# LEDSync_AR.net
KiCad netlist of a schematic drawn in EAGLE
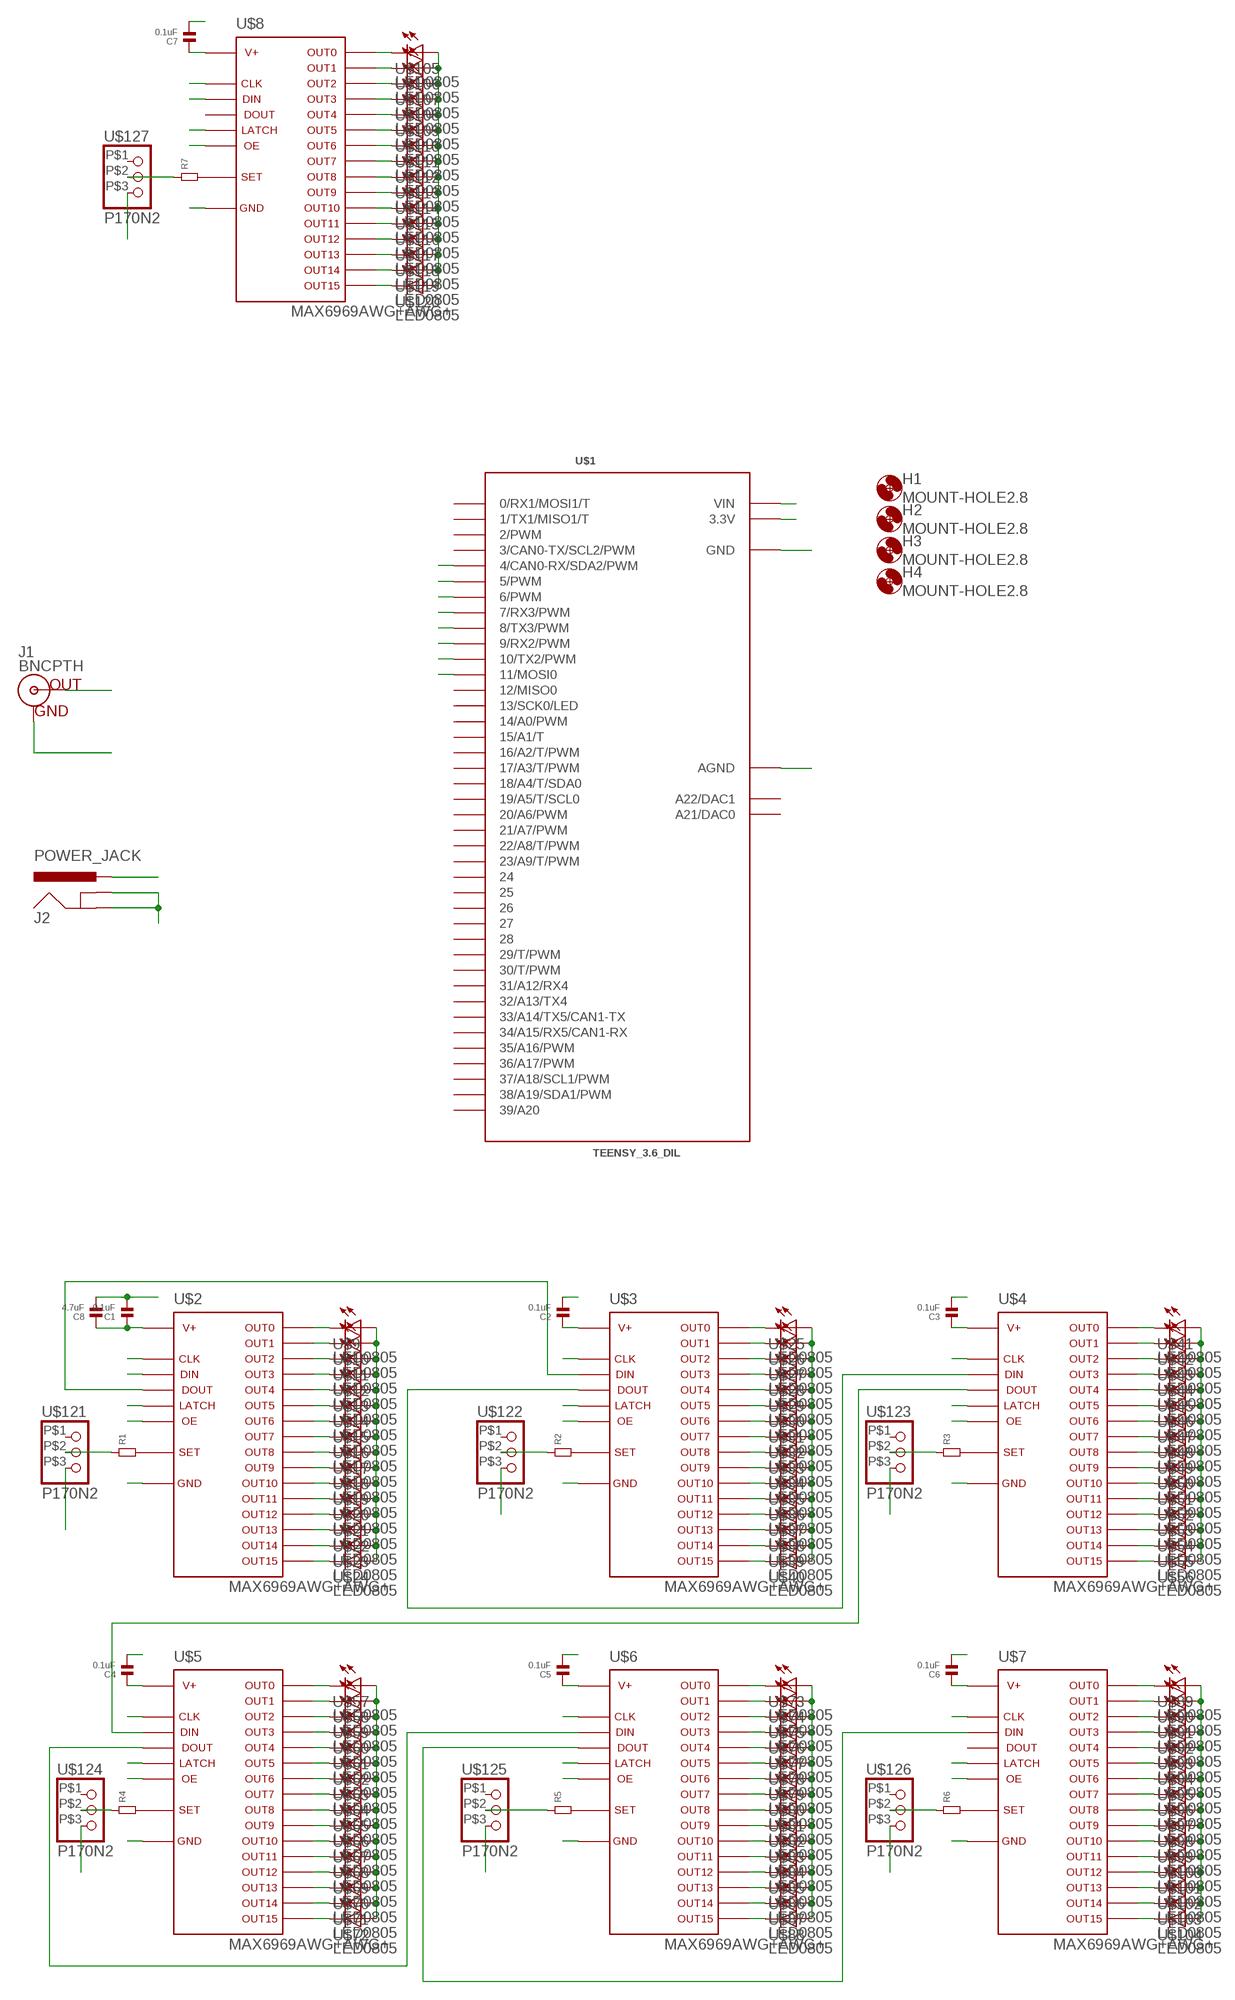
[diagram p0: schematic, sheet 1]

(export (version "E")
  (design (tool "Eeschema 10.0.6"))
  (components
    (comp (ref "C1")
      (value "0.1uF")
      (footprint "eagle-import:0805")
      (libsource (lib "eagle-import") (part "CAPACITOR.0805"))
    )
    (comp (ref "C2")
      (value "0.1uF")
      (footprint "eagle-import:0805")
      (libsource (lib "eagle-import") (part "CAPACITOR.0805"))
    )
    (comp (ref "C3")
      (value "0.1uF")
      (footprint "eagle-import:0805")
      (libsource (lib "eagle-import") (part "CAPACITOR.0805"))
    )
    (comp (ref "C4")
      (value "0.1uF")
      (footprint "eagle-import:0805")
      (libsource (lib "eagle-import") (part "CAPACITOR.0805"))
    )
    (comp (ref "C5")
      (value "0.1uF")
      (footprint "eagle-import:0805")
      (libsource (lib "eagle-import") (part "CAPACITOR.0805"))
    )
    (comp (ref "C6")
      (value "0.1uF")
      (footprint "eagle-import:0805")
      (libsource (lib "eagle-import") (part "CAPACITOR.0805"))
    )
    (comp (ref "C7")
      (value "0.1uF")
      (footprint "eagle-import:0805")
      (libsource (lib "eagle-import") (part "CAPACITOR.0805"))
    )
    (comp (ref "C8")
      (value "4.7uF")
      (footprint "eagle-import:0805")
      (libsource (lib "eagle-import") (part "CAPACITOR.0805"))
    )
    (comp (ref "H1")
      (value "MOUNT-HOLE2.8")
      (footprint "eagle-import:2,8")
      (libsource (lib "eagle-import") (part "MOUNT-HOLE2.8"))
    )
    (comp (ref "H2")
      (value "MOUNT-HOLE2.8")
      (footprint "eagle-import:2,8")
      (libsource (lib "eagle-import") (part "MOUNT-HOLE2.8"))
    )
    (comp (ref "H3")
      (value "MOUNT-HOLE2.8")
      (footprint "eagle-import:2,8")
      (libsource (lib "eagle-import") (part "MOUNT-HOLE2.8"))
    )
    (comp (ref "H4")
      (value "MOUNT-HOLE2.8")
      (footprint "eagle-import:2,8")
      (libsource (lib "eagle-import") (part "MOUNT-HOLE2.8"))
    )
    (comp (ref "J1")
      (value "BNCPTH")
      (footprint "eagle-import:BNC")
      (libsource (lib "eagle-import") (part "BNCPTH"))
    )
    (comp (ref "J2")
      (value "POWER_JACK")
      (footprint "eagle-import:POWER_JACK_PTH")
      (libsource (lib "eagle-import") (part "POWER_JACK"))
    )
    (comp (ref "R1")
      (value "RESISTOR.0805")
      (footprint "eagle-import:0805")
      (libsource (lib "eagle-import") (part "RESISTOR.0805"))
    )
    (comp (ref "R2")
      (value "RESISTOR.0805")
      (footprint "eagle-import:0805")
      (libsource (lib "eagle-import") (part "RESISTOR.0805"))
    )
    (comp (ref "R3")
      (value "RESISTOR.0805")
      (footprint "eagle-import:0805")
      (libsource (lib "eagle-import") (part "RESISTOR.0805"))
    )
    (comp (ref "R4")
      (value "RESISTOR.0805")
      (footprint "eagle-import:0805")
      (libsource (lib "eagle-import") (part "RESISTOR.0805"))
    )
    (comp (ref "R5")
      (value "RESISTOR.0805")
      (footprint "eagle-import:0805")
      (libsource (lib "eagle-import") (part "RESISTOR.0805"))
    )
    (comp (ref "R6")
      (value "RESISTOR.0805")
      (footprint "eagle-import:0805")
      (libsource (lib "eagle-import") (part "RESISTOR.0805"))
    )
    (comp (ref "R7")
      (value "RESISTOR.0805")
      (footprint "eagle-import:0805")
      (libsource (lib "eagle-import") (part "RESISTOR.0805"))
    )
    (comp (ref "U$1")
      (value "TEENSY_3.6_DIL")
      (footprint "eagle-import:TEENSY_3.6_DIL")
      (libsource (lib "eagle-import") (part "TEENSY_3.6_DIL"))
    )
    (comp (ref "U$2")
      (value "MAX6969AWG+AWG+")
      (footprint "eagle-import:SO24L")
      (libsource (lib "eagle-import") (part "MAX6969AWG+AWG+"))
    )
    (comp (ref "U$3")
      (value "MAX6969AWG+AWG+")
      (footprint "eagle-import:SO24L")
      (libsource (lib "eagle-import") (part "MAX6969AWG+AWG+"))
    )
    (comp (ref "U$4")
      (value "MAX6969AWG+AWG+")
      (footprint "eagle-import:SO24L")
      (libsource (lib "eagle-import") (part "MAX6969AWG+AWG+"))
    )
    (comp (ref "U$5")
      (value "MAX6969AWG+AWG+")
      (footprint "eagle-import:SO24L")
      (libsource (lib "eagle-import") (part "MAX6969AWG+AWG+"))
    )
    (comp (ref "U$6")
      (value "MAX6969AWG+AWG+")
      (footprint "eagle-import:SO24L")
      (libsource (lib "eagle-import") (part "MAX6969AWG+AWG+"))
    )
    (comp (ref "U$7")
      (value "MAX6969AWG+AWG+")
      (footprint "eagle-import:SO24L")
      (libsource (lib "eagle-import") (part "MAX6969AWG+AWG+"))
    )
    (comp (ref "U$8")
      (value "MAX6969AWG+AWG+")
      (footprint "eagle-import:SO24L")
      (libsource (lib "eagle-import") (part "MAX6969AWG+AWG+"))
    )
    (comp (ref "U$9")
      (value "LED0805")
      (footprint "eagle-import:0805")
      (libsource (lib "eagle-import") (part "LED0805"))
    )
    (comp (ref "U$10")
      (value "LED0805")
      (footprint "eagle-import:0805")
      (libsource (lib "eagle-import") (part "LED0805"))
    )
    (comp (ref "U$11")
      (value "LED0805")
      (footprint "eagle-import:0805")
      (libsource (lib "eagle-import") (part "LED0805"))
    )
    (comp (ref "U$12")
      (value "LED0805")
      (footprint "eagle-import:0805")
      (libsource (lib "eagle-import") (part "LED0805"))
    )
    (comp (ref "U$13")
      (value "LED0805")
      (footprint "eagle-import:0805")
      (libsource (lib "eagle-import") (part "LED0805"))
    )
    (comp (ref "U$14")
      (value "LED0805")
      (footprint "eagle-import:0805")
      (libsource (lib "eagle-import") (part "LED0805"))
    )
    (comp (ref "U$15")
      (value "LED0805")
      (footprint "eagle-import:0805")
      (libsource (lib "eagle-import") (part "LED0805"))
    )
    (comp (ref "U$16")
      (value "LED0805")
      (footprint "eagle-import:0805")
      (libsource (lib "eagle-import") (part "LED0805"))
    )
    (comp (ref "U$17")
      (value "LED0805")
      (footprint "eagle-import:0805")
      (libsource (lib "eagle-import") (part "LED0805"))
    )
    (comp (ref "U$18")
      (value "LED0805")
      (footprint "eagle-import:0805")
      (libsource (lib "eagle-import") (part "LED0805"))
    )
    (comp (ref "U$19")
      (value "LED0805")
      (footprint "eagle-import:0805")
      (libsource (lib "eagle-import") (part "LED0805"))
    )
    (comp (ref "U$20")
      (value "LED0805")
      (footprint "eagle-import:0805")
      (libsource (lib "eagle-import") (part "LED0805"))
    )
    (comp (ref "U$21")
      (value "LED0805")
      (footprint "eagle-import:0805")
      (libsource (lib "eagle-import") (part "LED0805"))
    )
    (comp (ref "U$22")
      (value "LED0805")
      (footprint "eagle-import:0805")
      (libsource (lib "eagle-import") (part "LED0805"))
    )
    (comp (ref "U$23")
      (value "LED0805")
      (footprint "eagle-import:0805")
      (libsource (lib "eagle-import") (part "LED0805"))
    )
    (comp (ref "U$24")
      (value "LED0805")
      (footprint "eagle-import:0805")
      (libsource (lib "eagle-import") (part "LED0805"))
    )
    (comp (ref "U$25")
      (value "LED0805")
      (footprint "eagle-import:0805")
      (libsource (lib "eagle-import") (part "LED0805"))
    )
    (comp (ref "U$26")
      (value "LED0805")
      (footprint "eagle-import:0805")
      (libsource (lib "eagle-import") (part "LED0805"))
    )
    (comp (ref "U$27")
      (value "LED0805")
      (footprint "eagle-import:0805")
      (libsource (lib "eagle-import") (part "LED0805"))
    )
    (comp (ref "U$28")
      (value "LED0805")
      (footprint "eagle-import:0805")
      (libsource (lib "eagle-import") (part "LED0805"))
    )
    (comp (ref "U$29")
      (value "LED0805")
      (footprint "eagle-import:0805")
      (libsource (lib "eagle-import") (part "LED0805"))
    )
    (comp (ref "U$30")
      (value "LED0805")
      (footprint "eagle-import:0805")
      (libsource (lib "eagle-import") (part "LED0805"))
    )
    (comp (ref "U$31")
      (value "LED0805")
      (footprint "eagle-import:0805")
      (libsource (lib "eagle-import") (part "LED0805"))
    )
    (comp (ref "U$32")
      (value "LED0805")
      (footprint "eagle-import:0805")
      (libsource (lib "eagle-import") (part "LED0805"))
    )
    (comp (ref "U$33")
      (value "LED0805")
      (footprint "eagle-import:0805")
      (libsource (lib "eagle-import") (part "LED0805"))
    )
    (comp (ref "U$34")
      (value "LED0805")
      (footprint "eagle-import:0805")
      (libsource (lib "eagle-import") (part "LED0805"))
    )
    (comp (ref "U$35")
      (value "LED0805")
      (footprint "eagle-import:0805")
      (libsource (lib "eagle-import") (part "LED0805"))
    )
    (comp (ref "U$36")
      (value "LED0805")
      (footprint "eagle-import:0805")
      (libsource (lib "eagle-import") (part "LED0805"))
    )
    (comp (ref "U$37")
      (value "LED0805")
      (footprint "eagle-import:0805")
      (libsource (lib "eagle-import") (part "LED0805"))
    )
    (comp (ref "U$38")
      (value "LED0805")
      (footprint "eagle-import:0805")
      (libsource (lib "eagle-import") (part "LED0805"))
    )
    (comp (ref "U$39")
      (value "LED0805")
      (footprint "eagle-import:0805")
      (libsource (lib "eagle-import") (part "LED0805"))
    )
    (comp (ref "U$40")
      (value "LED0805")
      (footprint "eagle-import:0805")
      (libsource (lib "eagle-import") (part "LED0805"))
    )
    (comp (ref "U$41")
      (value "LED0805")
      (footprint "eagle-import:0805")
      (libsource (lib "eagle-import") (part "LED0805"))
    )
    (comp (ref "U$42")
      (value "LED0805")
      (footprint "eagle-import:0805")
      (libsource (lib "eagle-import") (part "LED0805"))
    )
    (comp (ref "U$43")
      (value "LED0805")
      (footprint "eagle-import:0805")
      (libsource (lib "eagle-import") (part "LED0805"))
    )
    (comp (ref "U$44")
      (value "LED0805")
      (footprint "eagle-import:0805")
      (libsource (lib "eagle-import") (part "LED0805"))
    )
    (comp (ref "U$45")
      (value "LED0805")
      (footprint "eagle-import:0805")
      (libsource (lib "eagle-import") (part "LED0805"))
    )
    (comp (ref "U$46")
      (value "LED0805")
      (footprint "eagle-import:0805")
      (libsource (lib "eagle-import") (part "LED0805"))
    )
    (comp (ref "U$47")
      (value "LED0805")
      (footprint "eagle-import:0805")
      (libsource (lib "eagle-import") (part "LED0805"))
    )
    (comp (ref "U$48")
      (value "LED0805")
      (footprint "eagle-import:0805")
      (libsource (lib "eagle-import") (part "LED0805"))
    )
    (comp (ref "U$49")
      (value "LED0805")
      (footprint "eagle-import:0805")
      (libsource (lib "eagle-import") (part "LED0805"))
    )
    (comp (ref "U$50")
      (value "LED0805")
      (footprint "eagle-import:0805")
      (libsource (lib "eagle-import") (part "LED0805"))
    )
    (comp (ref "U$51")
      (value "LED0805")
      (footprint "eagle-import:0805")
      (libsource (lib "eagle-import") (part "LED0805"))
    )
    (comp (ref "U$52")
      (value "LED0805")
      (footprint "eagle-import:0805")
      (libsource (lib "eagle-import") (part "LED0805"))
    )
    (comp (ref "U$53")
      (value "LED0805")
      (footprint "eagle-import:0805")
      (libsource (lib "eagle-import") (part "LED0805"))
    )
    (comp (ref "U$54")
      (value "LED0805")
      (footprint "eagle-import:0805")
      (libsource (lib "eagle-import") (part "LED0805"))
    )
    (comp (ref "U$55")
      (value "LED0805")
      (footprint "eagle-import:0805")
      (libsource (lib "eagle-import") (part "LED0805"))
    )
    (comp (ref "U$56")
      (value "LED0805")
      (footprint "eagle-import:0805")
      (libsource (lib "eagle-import") (part "LED0805"))
    )
    (comp (ref "U$57")
      (value "LED0805")
      (footprint "eagle-import:0805")
      (libsource (lib "eagle-import") (part "LED0805"))
    )
    (comp (ref "U$58")
      (value "LED0805")
      (footprint "eagle-import:0805")
      (libsource (lib "eagle-import") (part "LED0805"))
    )
    (comp (ref "U$59")
      (value "LED0805")
      (footprint "eagle-import:0805")
      (libsource (lib "eagle-import") (part "LED0805"))
    )
    (comp (ref "U$60")
      (value "LED0805")
      (footprint "eagle-import:0805")
      (libsource (lib "eagle-import") (part "LED0805"))
    )
    (comp (ref "U$61")
      (value "LED0805")
      (footprint "eagle-import:0805")
      (libsource (lib "eagle-import") (part "LED0805"))
    )
    (comp (ref "U$62")
      (value "LED0805")
      (footprint "eagle-import:0805")
      (libsource (lib "eagle-import") (part "LED0805"))
    )
    (comp (ref "U$63")
      (value "LED0805")
      (footprint "eagle-import:0805")
      (libsource (lib "eagle-import") (part "LED0805"))
    )
    (comp (ref "U$64")
      (value "LED0805")
      (footprint "eagle-import:0805")
      (libsource (lib "eagle-import") (part "LED0805"))
    )
    (comp (ref "U$65")
      (value "LED0805")
      (footprint "eagle-import:0805")
      (libsource (lib "eagle-import") (part "LED0805"))
    )
    (comp (ref "U$66")
      (value "LED0805")
      (footprint "eagle-import:0805")
      (libsource (lib "eagle-import") (part "LED0805"))
    )
    (comp (ref "U$67")
      (value "LED0805")
      (footprint "eagle-import:0805")
      (libsource (lib "eagle-import") (part "LED0805"))
    )
    (comp (ref "U$68")
      (value "LED0805")
      (footprint "eagle-import:0805")
      (libsource (lib "eagle-import") (part "LED0805"))
    )
    (comp (ref "U$69")
      (value "LED0805")
      (footprint "eagle-import:0805")
      (libsource (lib "eagle-import") (part "LED0805"))
    )
    (comp (ref "U$70")
      (value "LED0805")
      (footprint "eagle-import:0805")
      (libsource (lib "eagle-import") (part "LED0805"))
    )
    (comp (ref "U$71")
      (value "LED0805")
      (footprint "eagle-import:0805")
      (libsource (lib "eagle-import") (part "LED0805"))
    )
    (comp (ref "U$72")
      (value "LED0805")
      (footprint "eagle-import:0805")
      (libsource (lib "eagle-import") (part "LED0805"))
    )
    (comp (ref "U$73")
      (value "LED0805")
      (footprint "eagle-import:0805")
      (libsource (lib "eagle-import") (part "LED0805"))
    )
    (comp (ref "U$74")
      (value "LED0805")
      (footprint "eagle-import:0805")
      (libsource (lib "eagle-import") (part "LED0805"))
    )
    (comp (ref "U$75")
      (value "LED0805")
      (footprint "eagle-import:0805")
      (libsource (lib "eagle-import") (part "LED0805"))
    )
    (comp (ref "U$76")
      (value "LED0805")
      (footprint "eagle-import:0805")
      (libsource (lib "eagle-import") (part "LED0805"))
    )
    (comp (ref "U$77")
      (value "LED0805")
      (footprint "eagle-import:0805")
      (libsource (lib "eagle-import") (part "LED0805"))
    )
    (comp (ref "U$78")
      (value "LED0805")
      (footprint "eagle-import:0805")
      (libsource (lib "eagle-import") (part "LED0805"))
    )
    (comp (ref "U$79")
      (value "LED0805")
      (footprint "eagle-import:0805")
      (libsource (lib "eagle-import") (part "LED0805"))
    )
    (comp (ref "U$80")
      (value "LED0805")
      (footprint "eagle-import:0805")
      (libsource (lib "eagle-import") (part "LED0805"))
    )
    (comp (ref "U$81")
      (value "LED0805")
      (footprint "eagle-import:0805")
      (libsource (lib "eagle-import") (part "LED0805"))
    )
    (comp (ref "U$82")
      (value "LED0805")
      (footprint "eagle-import:0805")
      (libsource (lib "eagle-import") (part "LED0805"))
    )
    (comp (ref "U$83")
      (value "LED0805")
      (footprint "eagle-import:0805")
      (libsource (lib "eagle-import") (part "LED0805"))
    )
    (comp (ref "U$84")
      (value "LED0805")
      (footprint "eagle-import:0805")
      (libsource (lib "eagle-import") (part "LED0805"))
    )
    (comp (ref "U$85")
      (value "LED0805")
      (footprint "eagle-import:0805")
      (libsource (lib "eagle-import") (part "LED0805"))
    )
    (comp (ref "U$86")
      (value "LED0805")
      (footprint "eagle-import:0805")
      (libsource (lib "eagle-import") (part "LED0805"))
    )
    (comp (ref "U$87")
      (value "LED0805")
      (footprint "eagle-import:0805")
      (libsource (lib "eagle-import") (part "LED0805"))
    )
    (comp (ref "U$88")
      (value "LED0805")
      (footprint "eagle-import:0805")
      (libsource (lib "eagle-import") (part "LED0805"))
    )
    (comp (ref "U$89")
      (value "LED0805")
      (footprint "eagle-import:0805")
      (libsource (lib "eagle-import") (part "LED0805"))
    )
    (comp (ref "U$90")
      (value "LED0805")
      (footprint "eagle-import:0805")
      (libsource (lib "eagle-import") (part "LED0805"))
    )
    (comp (ref "U$91")
      (value "LED0805")
      (footprint "eagle-import:0805")
      (libsource (lib "eagle-import") (part "LED0805"))
    )
    (comp (ref "U$92")
      (value "LED0805")
      (footprint "eagle-import:0805")
      (libsource (lib "eagle-import") (part "LED0805"))
    )
    (comp (ref "U$93")
      (value "LED0805")
      (footprint "eagle-import:0805")
      (libsource (lib "eagle-import") (part "LED0805"))
    )
    (comp (ref "U$94")
      (value "LED0805")
      (footprint "eagle-import:0805")
      (libsource (lib "eagle-import") (part "LED0805"))
    )
    (comp (ref "U$95")
      (value "LED0805")
      (footprint "eagle-import:0805")
      (libsource (lib "eagle-import") (part "LED0805"))
    )
    (comp (ref "U$96")
      (value "LED0805")
      (footprint "eagle-import:0805")
      (libsource (lib "eagle-import") (part "LED0805"))
    )
    (comp (ref "U$97")
      (value "LED0805")
      (footprint "eagle-import:0805")
      (libsource (lib "eagle-import") (part "LED0805"))
    )
    (comp (ref "U$98")
      (value "LED0805")
      (footprint "eagle-import:0805")
      (libsource (lib "eagle-import") (part "LED0805"))
    )
    (comp (ref "U$99")
      (value "LED0805")
      (footprint "eagle-import:0805")
      (libsource (lib "eagle-import") (part "LED0805"))
    )
    (comp (ref "U$100")
      (value "LED0805")
      (footprint "eagle-import:0805")
      (libsource (lib "eagle-import") (part "LED0805"))
    )
    (comp (ref "U$101")
      (value "LED0805")
      (footprint "eagle-import:0805")
      (libsource (lib "eagle-import") (part "LED0805"))
    )
    (comp (ref "U$102")
      (value "LED0805")
      (footprint "eagle-import:0805")
      (libsource (lib "eagle-import") (part "LED0805"))
    )
    (comp (ref "U$103")
      (value "LED0805")
      (footprint "eagle-import:0805")
      (libsource (lib "eagle-import") (part "LED0805"))
    )
    (comp (ref "U$104")
      (value "LED0805")
      (footprint "eagle-import:0805")
      (libsource (lib "eagle-import") (part "LED0805"))
    )
    (comp (ref "U$105")
      (value "LED0805")
      (footprint "eagle-import:0805")
      (libsource (lib "eagle-import") (part "LED0805"))
    )
    (comp (ref "U$106")
      (value "LED0805")
      (footprint "eagle-import:0805")
      (libsource (lib "eagle-import") (part "LED0805"))
    )
    (comp (ref "U$107")
      (value "LED0805")
      (footprint "eagle-import:0805")
      (libsource (lib "eagle-import") (part "LED0805"))
    )
    (comp (ref "U$108")
      (value "LED0805")
      (footprint "eagle-import:0805")
      (libsource (lib "eagle-import") (part "LED0805"))
    )
    (comp (ref "U$109")
      (value "LED0805")
      (footprint "eagle-import:0805")
      (libsource (lib "eagle-import") (part "LED0805"))
    )
    (comp (ref "U$110")
      (value "LED0805")
      (footprint "eagle-import:0805")
      (libsource (lib "eagle-import") (part "LED0805"))
    )
    (comp (ref "U$111")
      (value "LED0805")
      (footprint "eagle-import:0805")
      (libsource (lib "eagle-import") (part "LED0805"))
    )
    (comp (ref "U$112")
      (value "LED0805")
      (footprint "eagle-import:0805")
      (libsource (lib "eagle-import") (part "LED0805"))
    )
    (comp (ref "U$113")
      (value "LED0805")
      (footprint "eagle-import:0805")
      (libsource (lib "eagle-import") (part "LED0805"))
    )
    (comp (ref "U$114")
      (value "LED0805")
      (footprint "eagle-import:0805")
      (libsource (lib "eagle-import") (part "LED0805"))
    )
    (comp (ref "U$115")
      (value "LED0805")
      (footprint "eagle-import:0805")
      (libsource (lib "eagle-import") (part "LED0805"))
    )
    (comp (ref "U$116")
      (value "LED0805")
      (footprint "eagle-import:0805")
      (libsource (lib "eagle-import") (part "LED0805"))
    )
    (comp (ref "U$117")
      (value "LED0805")
      (footprint "eagle-import:0805")
      (libsource (lib "eagle-import") (part "LED0805"))
    )
    (comp (ref "U$118")
      (value "LED0805")
      (footprint "eagle-import:0805")
      (libsource (lib "eagle-import") (part "LED0805"))
    )
    (comp (ref "U$119")
      (value "LED0805")
      (footprint "eagle-import:0805")
      (libsource (lib "eagle-import") (part "LED0805"))
    )
    (comp (ref "U$120")
      (value "LED0805")
      (footprint "eagle-import:0805")
      (libsource (lib "eagle-import") (part "LED0805"))
    )
    (comp (ref "U$121")
      (value "P170N2")
      (footprint "eagle-import:P170N2")
      (libsource (lib "eagle-import") (part "P170N2"))
    )
    (comp (ref "U$122")
      (value "P170N2")
      (footprint "eagle-import:P170N2")
      (libsource (lib "eagle-import") (part "P170N2"))
    )
    (comp (ref "U$123")
      (value "P170N2")
      (footprint "eagle-import:P170N2")
      (libsource (lib "eagle-import") (part "P170N2"))
    )
    (comp (ref "U$124")
      (value "P170N2")
      (footprint "eagle-import:P170N2")
      (libsource (lib "eagle-import") (part "P170N2"))
    )
    (comp (ref "U$125")
      (value "P170N2")
      (footprint "eagle-import:P170N2")
      (libsource (lib "eagle-import") (part "P170N2"))
    )
    (comp (ref "U$126")
      (value "P170N2")
      (footprint "eagle-import:P170N2")
      (libsource (lib "eagle-import") (part "P170N2"))
    )
    (comp (ref "U$127")
      (value "P170N2")
      (footprint "eagle-import:P170N2")
      (libsource (lib "eagle-import") (part "P170N2"))
    )
  )
  (nets
    (net (code "1") (name "/GND") (class "Default")
      (node (ref "C1") (pin "2") (pinfunction "2_2") (pintype "bidirectional"))
      (node (ref "C2") (pin "2") (pinfunction "2_2") (pintype "bidirectional"))
      (node (ref "C3") (pin "2") (pinfunction "2_2") (pintype "bidirectional"))
      (node (ref "C4") (pin "2") (pinfunction "2_2") (pintype "bidirectional"))
      (node (ref "C5") (pin "2") (pinfunction "2_2") (pintype "bidirectional"))
      (node (ref "C6") (pin "2") (pinfunction "2_2") (pintype "bidirectional"))
      (node (ref "C7") (pin "2") (pinfunction "2_2") (pintype "bidirectional"))
      (node (ref "C8") (pin "2") (pinfunction "2_2") (pintype "bidirectional"))
      (node (ref "J1") (pin "GND") (pinfunction "GND_GND") (pintype "bidirectional"))
      (node (ref "J2") (pin "GND") (pinfunction "GND_GND") (pintype "bidirectional"))
      (node (ref "J2") (pin "GNDBREAK") (pinfunction "GNDBREAK_GNDBREAK") (pintype "bidirectional"))
      (node (ref "U$1") (pin "AGND") (pinfunction "AGND_AGND") (pintype "power_in"))
      (node (ref "U$1") (pin "GND") (pinfunction "GND_GND") (pintype "power_in"))
      (node (ref "U$1") (pin "GND1") (pinfunction "GND_GND1") (pintype "power_in"))
      (node (ref "U$121") (pin "P$3") (pinfunction "3_P$3") (pintype "passive"))
      (node (ref "U$122") (pin "P$3") (pinfunction "3_P$3") (pintype "passive"))
      (node (ref "U$123") (pin "P$3") (pinfunction "3_P$3") (pintype "passive"))
      (node (ref "U$124") (pin "P$3") (pinfunction "3_P$3") (pintype "passive"))
      (node (ref "U$125") (pin "P$3") (pinfunction "3_P$3") (pintype "passive"))
      (node (ref "U$126") (pin "P$3") (pinfunction "3_P$3") (pintype "passive"))
      (node (ref "U$127") (pin "P$3") (pinfunction "3_P$3") (pintype "passive"))
      (node (ref "U$2") (pin "1") (pinfunction "P$1_1") (pintype "power_in"))
      (node (ref "U$3") (pin "1") (pinfunction "P$1_1") (pintype "power_in"))
      (node (ref "U$4") (pin "1") (pinfunction "P$1_1") (pintype "power_in"))
      (node (ref "U$5") (pin "1") (pinfunction "P$1_1") (pintype "power_in"))
      (node (ref "U$6") (pin "1") (pinfunction "P$1_1") (pintype "power_in"))
      (node (ref "U$7") (pin "1") (pinfunction "P$1_1") (pintype "power_in"))
      (node (ref "U$8") (pin "1") (pinfunction "P$1_1") (pintype "power_in"))
    )
    (net (code "2") (name "/G_CLK") (class "Default")
      (node (ref "U$1") (pin "5") (pinfunction "5/PWM_5") (pintype "bidirectional"))
      (node (ref "U$2") (pin "3") (pinfunction "P$3_3") (pintype "input"))
      (node (ref "U$3") (pin "3") (pinfunction "P$3_3") (pintype "input"))
      (node (ref "U$4") (pin "3") (pinfunction "P$3_3") (pintype "input"))
      (node (ref "U$5") (pin "3") (pinfunction "P$3_3") (pintype "input"))
      (node (ref "U$6") (pin "3") (pinfunction "P$3_3") (pintype "input"))
      (node (ref "U$7") (pin "3") (pinfunction "P$3_3") (pintype "input"))
    )
    (net (code "3") (name "/G_D") (class "Default")
      (node (ref "U$1") (pin "4") (pinfunction "4/CAN0-RX/SDA2/PWM_4") (pintype "bidirectional"))
      (node (ref "U$2") (pin "2") (pinfunction "P$2_2") (pintype "input"))
    )
    (net (code "4") (name "/G_LE") (class "Default")
      (node (ref "J1") (pin "S") (pinfunction "OUT_S") (pintype "bidirectional"))
      (node (ref "U$1") (pin "6") (pinfunction "6/PWM_6") (pintype "bidirectional"))
      (node (ref "U$2") (pin "4") (pinfunction "P$4_4") (pintype "input"))
      (node (ref "U$3") (pin "4") (pinfunction "P$4_4") (pintype "input"))
      (node (ref "U$4") (pin "4") (pinfunction "P$4_4") (pintype "input"))
      (node (ref "U$5") (pin "4") (pinfunction "P$4_4") (pintype "input"))
      (node (ref "U$6") (pin "4") (pinfunction "P$4_4") (pintype "input"))
      (node (ref "U$7") (pin "4") (pinfunction "P$4_4") (pintype "input"))
    )
    (net (code "5") (name "/G_OE") (class "Default")
      (node (ref "U$1") (pin "7") (pinfunction "7/RX3/PWM_7") (pintype "bidirectional"))
      (node (ref "U$2") (pin "21") (pinfunction "P$21_21") (pintype "input"))
      (node (ref "U$3") (pin "21") (pinfunction "P$21_21") (pintype "input"))
      (node (ref "U$4") (pin "21") (pinfunction "P$21_21") (pintype "input"))
      (node (ref "U$5") (pin "21") (pinfunction "P$21_21") (pintype "input"))
      (node (ref "U$6") (pin "21") (pinfunction "P$21_21") (pintype "input"))
      (node (ref "U$7") (pin "21") (pinfunction "P$21_21") (pintype "input"))
    )
    (net (code "6") (name "/T_CLK") (class "Default")
      (node (ref "U$1") (pin "9") (pinfunction "9/RX2/PWM_9") (pintype "bidirectional"))
      (node (ref "U$8") (pin "3") (pinfunction "P$3_3") (pintype "input"))
    )
    (net (code "7") (name "/T_D") (class "Default")
      (node (ref "U$1") (pin "8") (pinfunction "8/TX3/PWM_8") (pintype "bidirectional"))
      (node (ref "U$8") (pin "2") (pinfunction "P$2_2") (pintype "input"))
    )
    (net (code "8") (name "/T_LE") (class "Default")
      (node (ref "U$1") (pin "10") (pinfunction "10/TX2/PWM_10") (pintype "bidirectional"))
      (node (ref "U$8") (pin "4") (pinfunction "P$4_4") (pintype "input"))
    )
    (net (code "9") (name "/T_OE") (class "Default")
      (node (ref "U$1") (pin "11") (pinfunction "11/MOSI0_11") (pintype "bidirectional"))
      (node (ref "U$8") (pin "21") (pinfunction "P$21_21") (pintype "input"))
    )
    (net (code "10") (name "/VIN") (class "Default")
      (node (ref "C1") (pin "1") (pinfunction "1_1") (pintype "bidirectional"))
      (node (ref "C2") (pin "1") (pinfunction "1_1") (pintype "bidirectional"))
      (node (ref "C3") (pin "1") (pinfunction "1_1") (pintype "bidirectional"))
      (node (ref "C4") (pin "1") (pinfunction "1_1") (pintype "bidirectional"))
      (node (ref "C5") (pin "1") (pinfunction "1_1") (pintype "bidirectional"))
      (node (ref "C6") (pin "1") (pinfunction "1_1") (pintype "bidirectional"))
      (node (ref "C7") (pin "1") (pinfunction "1_1") (pintype "bidirectional"))
      (node (ref "C8") (pin "1") (pinfunction "1_1") (pintype "bidirectional"))
      (node (ref "J2") (pin "PWR") (pinfunction "PWR_PWR") (pintype "bidirectional"))
      (node (ref "U$1") (pin "VIN") (pinfunction "VIN_VIN") (pintype "power_in"))
      (node (ref "U$10") (pin "1") (pinfunction "A_1") (pintype "passive"))
      (node (ref "U$100") (pin "1") (pinfunction "A_1") (pintype "passive"))
      (node (ref "U$101") (pin "1") (pinfunction "A_1") (pintype "passive"))
      (node (ref "U$102") (pin "1") (pinfunction "A_1") (pintype "passive"))
      (node (ref "U$103") (pin "1") (pinfunction "A_1") (pintype "passive"))
      (node (ref "U$104") (pin "1") (pinfunction "A_1") (pintype "passive"))
      (node (ref "U$105") (pin "1") (pinfunction "A_1") (pintype "passive"))
      (node (ref "U$106") (pin "1") (pinfunction "A_1") (pintype "passive"))
      (node (ref "U$107") (pin "1") (pinfunction "A_1") (pintype "passive"))
      (node (ref "U$108") (pin "1") (pinfunction "A_1") (pintype "passive"))
      (node (ref "U$109") (pin "1") (pinfunction "A_1") (pintype "passive"))
      (node (ref "U$11") (pin "1") (pinfunction "A_1") (pintype "passive"))
      (node (ref "U$110") (pin "1") (pinfunction "A_1") (pintype "passive"))
      (node (ref "U$111") (pin "1") (pinfunction "A_1") (pintype "passive"))
      (node (ref "U$112") (pin "1") (pinfunction "A_1") (pintype "passive"))
      (node (ref "U$113") (pin "1") (pinfunction "A_1") (pintype "passive"))
      (node (ref "U$114") (pin "1") (pinfunction "A_1") (pintype "passive"))
      (node (ref "U$115") (pin "1") (pinfunction "A_1") (pintype "passive"))
      (node (ref "U$116") (pin "1") (pinfunction "A_1") (pintype "passive"))
      (node (ref "U$117") (pin "1") (pinfunction "A_1") (pintype "passive"))
      (node (ref "U$118") (pin "1") (pinfunction "A_1") (pintype "passive"))
      (node (ref "U$119") (pin "1") (pinfunction "A_1") (pintype "passive"))
      (node (ref "U$12") (pin "1") (pinfunction "A_1") (pintype "passive"))
      (node (ref "U$120") (pin "1") (pinfunction "A_1") (pintype "passive"))
      (node (ref "U$13") (pin "1") (pinfunction "A_1") (pintype "passive"))
      (node (ref "U$14") (pin "1") (pinfunction "A_1") (pintype "passive"))
      (node (ref "U$15") (pin "1") (pinfunction "A_1") (pintype "passive"))
      (node (ref "U$16") (pin "1") (pinfunction "A_1") (pintype "passive"))
      (node (ref "U$17") (pin "1") (pinfunction "A_1") (pintype "passive"))
      (node (ref "U$18") (pin "1") (pinfunction "A_1") (pintype "passive"))
      (node (ref "U$19") (pin "1") (pinfunction "A_1") (pintype "passive"))
      (node (ref "U$2") (pin "24") (pinfunction "P$24_24") (pintype "power_in"))
      (node (ref "U$20") (pin "1") (pinfunction "A_1") (pintype "passive"))
      (node (ref "U$21") (pin "1") (pinfunction "A_1") (pintype "passive"))
      (node (ref "U$22") (pin "1") (pinfunction "A_1") (pintype "passive"))
      (node (ref "U$23") (pin "1") (pinfunction "A_1") (pintype "passive"))
      (node (ref "U$24") (pin "1") (pinfunction "A_1") (pintype "passive"))
      (node (ref "U$25") (pin "1") (pinfunction "A_1") (pintype "passive"))
      (node (ref "U$26") (pin "1") (pinfunction "A_1") (pintype "passive"))
      (node (ref "U$27") (pin "1") (pinfunction "A_1") (pintype "passive"))
      (node (ref "U$28") (pin "1") (pinfunction "A_1") (pintype "passive"))
      (node (ref "U$29") (pin "1") (pinfunction "A_1") (pintype "passive"))
      (node (ref "U$3") (pin "24") (pinfunction "P$24_24") (pintype "power_in"))
      (node (ref "U$30") (pin "1") (pinfunction "A_1") (pintype "passive"))
      (node (ref "U$31") (pin "1") (pinfunction "A_1") (pintype "passive"))
      (node (ref "U$32") (pin "1") (pinfunction "A_1") (pintype "passive"))
      (node (ref "U$33") (pin "1") (pinfunction "A_1") (pintype "passive"))
      (node (ref "U$34") (pin "1") (pinfunction "A_1") (pintype "passive"))
      (node (ref "U$35") (pin "1") (pinfunction "A_1") (pintype "passive"))
      (node (ref "U$36") (pin "1") (pinfunction "A_1") (pintype "passive"))
      (node (ref "U$37") (pin "1") (pinfunction "A_1") (pintype "passive"))
      (node (ref "U$38") (pin "1") (pinfunction "A_1") (pintype "passive"))
      (node (ref "U$39") (pin "1") (pinfunction "A_1") (pintype "passive"))
      (node (ref "U$4") (pin "24") (pinfunction "P$24_24") (pintype "power_in"))
      (node (ref "U$40") (pin "1") (pinfunction "A_1") (pintype "passive"))
      (node (ref "U$41") (pin "1") (pinfunction "A_1") (pintype "passive"))
      (node (ref "U$42") (pin "1") (pinfunction "A_1") (pintype "passive"))
      (node (ref "U$43") (pin "1") (pinfunction "A_1") (pintype "passive"))
      (node (ref "U$44") (pin "1") (pinfunction "A_1") (pintype "passive"))
      (node (ref "U$45") (pin "1") (pinfunction "A_1") (pintype "passive"))
      (node (ref "U$46") (pin "1") (pinfunction "A_1") (pintype "passive"))
      (node (ref "U$47") (pin "1") (pinfunction "A_1") (pintype "passive"))
      (node (ref "U$48") (pin "1") (pinfunction "A_1") (pintype "passive"))
      (node (ref "U$49") (pin "1") (pinfunction "A_1") (pintype "passive"))
      (node (ref "U$5") (pin "24") (pinfunction "P$24_24") (pintype "power_in"))
      (node (ref "U$50") (pin "1") (pinfunction "A_1") (pintype "passive"))
      (node (ref "U$51") (pin "1") (pinfunction "A_1") (pintype "passive"))
      (node (ref "U$52") (pin "1") (pinfunction "A_1") (pintype "passive"))
      (node (ref "U$53") (pin "1") (pinfunction "A_1") (pintype "passive"))
      (node (ref "U$54") (pin "1") (pinfunction "A_1") (pintype "passive"))
      (node (ref "U$55") (pin "1") (pinfunction "A_1") (pintype "passive"))
      (node (ref "U$56") (pin "1") (pinfunction "A_1") (pintype "passive"))
      (node (ref "U$57") (pin "1") (pinfunction "A_1") (pintype "passive"))
      (node (ref "U$58") (pin "1") (pinfunction "A_1") (pintype "passive"))
      (node (ref "U$59") (pin "1") (pinfunction "A_1") (pintype "passive"))
      (node (ref "U$6") (pin "24") (pinfunction "P$24_24") (pintype "power_in"))
      (node (ref "U$60") (pin "1") (pinfunction "A_1") (pintype "passive"))
      (node (ref "U$61") (pin "1") (pinfunction "A_1") (pintype "passive"))
      (node (ref "U$62") (pin "1") (pinfunction "A_1") (pintype "passive"))
      (node (ref "U$63") (pin "1") (pinfunction "A_1") (pintype "passive"))
      (node (ref "U$64") (pin "1") (pinfunction "A_1") (pintype "passive"))
      (node (ref "U$65") (pin "1") (pinfunction "A_1") (pintype "passive"))
      (node (ref "U$66") (pin "1") (pinfunction "A_1") (pintype "passive"))
      (node (ref "U$67") (pin "1") (pinfunction "A_1") (pintype "passive"))
      (node (ref "U$68") (pin "1") (pinfunction "A_1") (pintype "passive"))
      (node (ref "U$69") (pin "1") (pinfunction "A_1") (pintype "passive"))
      (node (ref "U$7") (pin "24") (pinfunction "P$24_24") (pintype "power_in"))
      (node (ref "U$70") (pin "1") (pinfunction "A_1") (pintype "passive"))
      (node (ref "U$71") (pin "1") (pinfunction "A_1") (pintype "passive"))
      (node (ref "U$72") (pin "1") (pinfunction "A_1") (pintype "passive"))
      (node (ref "U$73") (pin "1") (pinfunction "A_1") (pintype "passive"))
      (node (ref "U$74") (pin "1") (pinfunction "A_1") (pintype "passive"))
      (node (ref "U$75") (pin "1") (pinfunction "A_1") (pintype "passive"))
      (node (ref "U$76") (pin "1") (pinfunction "A_1") (pintype "passive"))
      (node (ref "U$77") (pin "1") (pinfunction "A_1") (pintype "passive"))
      (node (ref "U$78") (pin "1") (pinfunction "A_1") (pintype "passive"))
      (node (ref "U$79") (pin "1") (pinfunction "A_1") (pintype "passive"))
      (node (ref "U$8") (pin "24") (pinfunction "P$24_24") (pintype "power_in"))
      (node (ref "U$80") (pin "1") (pinfunction "A_1") (pintype "passive"))
      (node (ref "U$81") (pin "1") (pinfunction "A_1") (pintype "passive"))
      (node (ref "U$82") (pin "1") (pinfunction "A_1") (pintype "passive"))
      (node (ref "U$83") (pin "1") (pinfunction "A_1") (pintype "passive"))
      (node (ref "U$84") (pin "1") (pinfunction "A_1") (pintype "passive"))
      (node (ref "U$85") (pin "1") (pinfunction "A_1") (pintype "passive"))
      (node (ref "U$86") (pin "1") (pinfunction "A_1") (pintype "passive"))
      (node (ref "U$87") (pin "1") (pinfunction "A_1") (pintype "passive"))
      (node (ref "U$88") (pin "1") (pinfunction "A_1") (pintype "passive"))
      (node (ref "U$89") (pin "1") (pinfunction "A_1") (pintype "passive"))
      (node (ref "U$9") (pin "1") (pinfunction "A_1") (pintype "passive"))
      (node (ref "U$90") (pin "1") (pinfunction "A_1") (pintype "passive"))
      (node (ref "U$91") (pin "1") (pinfunction "A_1") (pintype "passive"))
      (node (ref "U$92") (pin "1") (pinfunction "A_1") (pintype "passive"))
      (node (ref "U$93") (pin "1") (pinfunction "A_1") (pintype "passive"))
      (node (ref "U$94") (pin "1") (pinfunction "A_1") (pintype "passive"))
      (node (ref "U$95") (pin "1") (pinfunction "A_1") (pintype "passive"))
      (node (ref "U$96") (pin "1") (pinfunction "A_1") (pintype "passive"))
      (node (ref "U$97") (pin "1") (pinfunction "A_1") (pintype "passive"))
      (node (ref "U$98") (pin "1") (pinfunction "A_1") (pintype "passive"))
      (node (ref "U$99") (pin "1") (pinfunction "A_1") (pintype "passive"))
    )
    (net (code "11") (name "Net-(U$1-3.3V-Pad3.3V3)") (class "Default")
      (node (ref "U$1") (pin "3.3V") (pinfunction "3.3V_3.3V") (pintype "power_in"))
      (node (ref "U$1") (pin "3.3V3") (pinfunction "3.3V_3.3V3") (pintype "power_in"))
    )
    (net (code "12") (name "Net-(U$2-P$5)") (class "Default")
      (node (ref "U$2") (pin "5") (pinfunction "P$5_5") (pintype "output"))
      (node (ref "U$9") (pin "2") (pinfunction "C_2") (pintype "passive"))
    )
    (net (code "13") (name "Net-(U$2-P$16)") (class "Default")
      (node (ref "U$2") (pin "16") (pinfunction "P$16_16") (pintype "output"))
      (node (ref "U$20") (pin "2") (pinfunction "C_2") (pintype "passive"))
    )
    (net (code "14") (name "Net-(U$2-P$17)") (class "Default")
      (node (ref "U$2") (pin "17") (pinfunction "P$17_17") (pintype "output"))
      (node (ref "U$21") (pin "2") (pinfunction "C_2") (pintype "passive"))
    )
    (net (code "15") (name "Net-(U$2-P$18)") (class "Default")
      (node (ref "U$2") (pin "18") (pinfunction "P$18_18") (pintype "output"))
      (node (ref "U$22") (pin "2") (pinfunction "C_2") (pintype "passive"))
    )
    (net (code "16") (name "Net-(U$2-P$19)") (class "Default")
      (node (ref "U$2") (pin "19") (pinfunction "P$19_19") (pintype "output"))
      (node (ref "U$23") (pin "2") (pinfunction "C_2") (pintype "passive"))
    )
    (net (code "17") (name "Net-(U$2-P$20)") (class "Default")
      (node (ref "U$2") (pin "20") (pinfunction "P$20_20") (pintype "output"))
      (node (ref "U$24") (pin "2") (pinfunction "C_2") (pintype "passive"))
    )
    (net (code "18") (name "Net-(U$2-P$22)") (class "Default")
      (node (ref "U$2") (pin "22") (pinfunction "P$22_22") (pintype "output"))
      (node (ref "U$3") (pin "2") (pinfunction "P$2_2") (pintype "input"))
    )
    (net (code "19") (name "Net-(U$2-P$23)") (class "Default")
      (node (ref "R1") (pin "2") (pinfunction "2_2") (pintype "bidirectional"))
      (node (ref "U$2") (pin "23") (pinfunction "P$23_23") (pintype "bidirectional"))
    )
    (net (code "20") (name "Net-(U$3-P$10)") (class "Default")
      (node (ref "U$3") (pin "10") (pinfunction "P$10_10") (pintype "output"))
      (node (ref "U$30") (pin "2") (pinfunction "C_2") (pintype "passive"))
    )
    (net (code "21") (name "Net-(U$3-P$11)") (class "Default")
      (node (ref "U$3") (pin "11") (pinfunction "P$11_11") (pintype "output"))
      (node (ref "U$31") (pin "2") (pinfunction "C_2") (pintype "passive"))
    )
    (net (code "22") (name "Net-(U$3-P$12)") (class "Default")
      (node (ref "U$3") (pin "12") (pinfunction "P$12_12") (pintype "output"))
      (node (ref "U$32") (pin "2") (pinfunction "C_2") (pintype "passive"))
    )
    (net (code "23") (name "Net-(U$3-P$13)") (class "Default")
      (node (ref "U$3") (pin "13") (pinfunction "P$13_13") (pintype "output"))
      (node (ref "U$33") (pin "2") (pinfunction "C_2") (pintype "passive"))
    )
    (net (code "24") (name "Net-(U$3-P$14)") (class "Default")
      (node (ref "U$3") (pin "14") (pinfunction "P$14_14") (pintype "output"))
      (node (ref "U$34") (pin "2") (pinfunction "C_2") (pintype "passive"))
    )
    (net (code "25") (name "Net-(U$3-P$15)") (class "Default")
      (node (ref "U$3") (pin "15") (pinfunction "P$15_15") (pintype "output"))
      (node (ref "U$35") (pin "2") (pinfunction "C_2") (pintype "passive"))
    )
    (net (code "26") (name "Net-(U$3-P$16)") (class "Default")
      (node (ref "U$3") (pin "16") (pinfunction "P$16_16") (pintype "output"))
      (node (ref "U$36") (pin "2") (pinfunction "C_2") (pintype "passive"))
    )
    (net (code "27") (name "Net-(U$3-P$17)") (class "Default")
      (node (ref "U$3") (pin "17") (pinfunction "P$17_17") (pintype "output"))
      (node (ref "U$37") (pin "2") (pinfunction "C_2") (pintype "passive"))
    )
    (net (code "28") (name "Net-(U$3-P$18)") (class "Default")
      (node (ref "U$3") (pin "18") (pinfunction "P$18_18") (pintype "output"))
      (node (ref "U$38") (pin "2") (pinfunction "C_2") (pintype "passive"))
    )
    (net (code "29") (name "Net-(U$3-P$19)") (class "Default")
      (node (ref "U$3") (pin "19") (pinfunction "P$19_19") (pintype "output"))
      (node (ref "U$39") (pin "2") (pinfunction "C_2") (pintype "passive"))
    )
    (net (code "30") (name "Net-(U$3-P$20)") (class "Default")
      (node (ref "U$3") (pin "20") (pinfunction "P$20_20") (pintype "output"))
      (node (ref "U$40") (pin "2") (pinfunction "C_2") (pintype "passive"))
    )
    (net (code "31") (name "Net-(U$3-P$22)") (class "Default")
      (node (ref "U$3") (pin "22") (pinfunction "P$22_22") (pintype "output"))
      (node (ref "U$4") (pin "2") (pinfunction "P$2_2") (pintype "input"))
    )
    (net (code "32") (name "Net-(U$3-P$23)") (class "Default")
      (node (ref "R2") (pin "2") (pinfunction "2_2") (pintype "bidirectional"))
      (node (ref "U$3") (pin "23") (pinfunction "P$23_23") (pintype "bidirectional"))
    )
    (net (code "33") (name "Net-(U$4-P$5)") (class "Default")
      (node (ref "U$4") (pin "5") (pinfunction "P$5_5") (pintype "output"))
      (node (ref "U$41") (pin "2") (pinfunction "C_2") (pintype "passive"))
    )
    (net (code "34") (name "Net-(U$4-P$6)") (class "Default")
      (node (ref "U$4") (pin "6") (pinfunction "P$6_6") (pintype "output"))
      (node (ref "U$42") (pin "2") (pinfunction "C_2") (pintype "passive"))
    )
    (net (code "35") (name "Net-(U$4-P$7)") (class "Default")
      (node (ref "U$4") (pin "7") (pinfunction "P$7_7") (pintype "output"))
      (node (ref "U$43") (pin "2") (pinfunction "C_2") (pintype "passive"))
    )
    (net (code "36") (name "Net-(U$4-P$8)") (class "Default")
      (node (ref "U$4") (pin "8") (pinfunction "P$8_8") (pintype "output"))
      (node (ref "U$44") (pin "2") (pinfunction "C_2") (pintype "passive"))
    )
    (net (code "37") (name "Net-(U$4-P$9)") (class "Default")
      (node (ref "U$4") (pin "9") (pinfunction "P$9_9") (pintype "output"))
      (node (ref "U$45") (pin "2") (pinfunction "C_2") (pintype "passive"))
    )
    (net (code "38") (name "Net-(U$4-P$10)") (class "Default")
      (node (ref "U$4") (pin "10") (pinfunction "P$10_10") (pintype "output"))
      (node (ref "U$46") (pin "2") (pinfunction "C_2") (pintype "passive"))
    )
    (net (code "39") (name "Net-(U$4-P$11)") (class "Default")
      (node (ref "U$4") (pin "11") (pinfunction "P$11_11") (pintype "output"))
      (node (ref "U$47") (pin "2") (pinfunction "C_2") (pintype "passive"))
    )
    (net (code "40") (name "Net-(U$4-P$12)") (class "Default")
      (node (ref "U$4") (pin "12") (pinfunction "P$12_12") (pintype "output"))
      (node (ref "U$48") (pin "2") (pinfunction "C_2") (pintype "passive"))
    )
    (net (code "41") (name "Net-(U$4-P$13)") (class "Default")
      (node (ref "U$4") (pin "13") (pinfunction "P$13_13") (pintype "output"))
      (node (ref "U$49") (pin "2") (pinfunction "C_2") (pintype "passive"))
    )
    (net (code "42") (name "Net-(U$4-P$14)") (class "Default")
      (node (ref "U$4") (pin "14") (pinfunction "P$14_14") (pintype "output"))
      (node (ref "U$50") (pin "2") (pinfunction "C_2") (pintype "passive"))
    )
    (net (code "43") (name "Net-(U$4-P$15)") (class "Default")
      (node (ref "U$4") (pin "15") (pinfunction "P$15_15") (pintype "output"))
      (node (ref "U$51") (pin "2") (pinfunction "C_2") (pintype "passive"))
    )
    (net (code "44") (name "Net-(U$4-P$16)") (class "Default")
      (node (ref "U$4") (pin "16") (pinfunction "P$16_16") (pintype "output"))
      (node (ref "U$52") (pin "2") (pinfunction "C_2") (pintype "passive"))
    )
    (net (code "45") (name "Net-(U$4-P$17)") (class "Default")
      (node (ref "U$4") (pin "17") (pinfunction "P$17_17") (pintype "output"))
      (node (ref "U$53") (pin "2") (pinfunction "C_2") (pintype "passive"))
    )
    (net (code "46") (name "Net-(U$4-P$18)") (class "Default")
      (node (ref "U$4") (pin "18") (pinfunction "P$18_18") (pintype "output"))
      (node (ref "U$54") (pin "2") (pinfunction "C_2") (pintype "passive"))
    )
    (net (code "47") (name "Net-(U$4-P$19)") (class "Default")
      (node (ref "U$4") (pin "19") (pinfunction "P$19_19") (pintype "output"))
      (node (ref "U$55") (pin "2") (pinfunction "C_2") (pintype "passive"))
    )
    (net (code "48") (name "Net-(U$4-P$20)") (class "Default")
      (node (ref "U$4") (pin "20") (pinfunction "P$20_20") (pintype "output"))
      (node (ref "U$56") (pin "2") (pinfunction "C_2") (pintype "passive"))
    )
    (net (code "49") (name "Net-(U$4-P$22)") (class "Default")
      (node (ref "U$4") (pin "22") (pinfunction "P$22_22") (pintype "output"))
      (node (ref "U$5") (pin "2") (pinfunction "P$2_2") (pintype "input"))
    )
    (net (code "50") (name "Net-(U$4-P$23)") (class "Default")
      (node (ref "R3") (pin "2") (pinfunction "2_2") (pintype "bidirectional"))
      (node (ref "U$4") (pin "23") (pinfunction "P$23_23") (pintype "bidirectional"))
    )
    (net (code "51") (name "Net-(U$5-P$5)") (class "Default")
      (node (ref "U$5") (pin "5") (pinfunction "P$5_5") (pintype "output"))
      (node (ref "U$57") (pin "2") (pinfunction "C_2") (pintype "passive"))
    )
    (net (code "52") (name "Net-(U$5-P$6)") (class "Default")
      (node (ref "U$5") (pin "6") (pinfunction "P$6_6") (pintype "output"))
      (node (ref "U$58") (pin "2") (pinfunction "C_2") (pintype "passive"))
    )
    (net (code "53") (name "Net-(U$5-P$7)") (class "Default")
      (node (ref "U$5") (pin "7") (pinfunction "P$7_7") (pintype "output"))
      (node (ref "U$59") (pin "2") (pinfunction "C_2") (pintype "passive"))
    )
    (net (code "54") (name "Net-(U$5-P$8)") (class "Default")
      (node (ref "U$5") (pin "8") (pinfunction "P$8_8") (pintype "output"))
      (node (ref "U$60") (pin "2") (pinfunction "C_2") (pintype "passive"))
    )
    (net (code "55") (name "Net-(U$5-P$9)") (class "Default")
      (node (ref "U$5") (pin "9") (pinfunction "P$9_9") (pintype "output"))
      (node (ref "U$61") (pin "2") (pinfunction "C_2") (pintype "passive"))
    )
    (net (code "56") (name "Net-(U$5-P$10)") (class "Default")
      (node (ref "U$5") (pin "10") (pinfunction "P$10_10") (pintype "output"))
      (node (ref "U$62") (pin "2") (pinfunction "C_2") (pintype "passive"))
    )
    (net (code "57") (name "Net-(U$5-P$11)") (class "Default")
      (node (ref "U$5") (pin "11") (pinfunction "P$11_11") (pintype "output"))
      (node (ref "U$63") (pin "2") (pinfunction "C_2") (pintype "passive"))
    )
    (net (code "58") (name "Net-(U$5-P$12)") (class "Default")
      (node (ref "U$5") (pin "12") (pinfunction "P$12_12") (pintype "output"))
      (node (ref "U$64") (pin "2") (pinfunction "C_2") (pintype "passive"))
    )
    (net (code "59") (name "Net-(U$5-P$13)") (class "Default")
      (node (ref "U$5") (pin "13") (pinfunction "P$13_13") (pintype "output"))
      (node (ref "U$65") (pin "2") (pinfunction "C_2") (pintype "passive"))
    )
    (net (code "60") (name "Net-(U$5-P$14)") (class "Default")
      (node (ref "U$5") (pin "14") (pinfunction "P$14_14") (pintype "output"))
      (node (ref "U$66") (pin "2") (pinfunction "C_2") (pintype "passive"))
    )
    (net (code "61") (name "Net-(U$5-P$15)") (class "Default")
      (node (ref "U$5") (pin "15") (pinfunction "P$15_15") (pintype "output"))
      (node (ref "U$67") (pin "2") (pinfunction "C_2") (pintype "passive"))
    )
    (net (code "62") (name "Net-(U$5-P$16)") (class "Default")
      (node (ref "U$5") (pin "16") (pinfunction "P$16_16") (pintype "output"))
      (node (ref "U$68") (pin "2") (pinfunction "C_2") (pintype "passive"))
    )
    (net (code "63") (name "Net-(U$5-P$17)") (class "Default")
      (node (ref "U$5") (pin "17") (pinfunction "P$17_17") (pintype "output"))
      (node (ref "U$69") (pin "2") (pinfunction "C_2") (pintype "passive"))
    )
    (net (code "64") (name "Net-(U$5-P$18)") (class "Default")
      (node (ref "U$5") (pin "18") (pinfunction "P$18_18") (pintype "output"))
      (node (ref "U$70") (pin "2") (pinfunction "C_2") (pintype "passive"))
    )
    (net (code "65") (name "Net-(U$5-P$19)") (class "Default")
      (node (ref "U$5") (pin "19") (pinfunction "P$19_19") (pintype "output"))
      (node (ref "U$71") (pin "2") (pinfunction "C_2") (pintype "passive"))
    )
    (net (code "66") (name "Net-(U$5-P$20)") (class "Default")
      (node (ref "U$5") (pin "20") (pinfunction "P$20_20") (pintype "output"))
      (node (ref "U$72") (pin "2") (pinfunction "C_2") (pintype "passive"))
    )
    (net (code "67") (name "Net-(U$5-P$22)") (class "Default")
      (node (ref "U$5") (pin "22") (pinfunction "P$22_22") (pintype "output"))
      (node (ref "U$6") (pin "2") (pinfunction "P$2_2") (pintype "input"))
    )
    (net (code "68") (name "Net-(U$5-P$23)") (class "Default")
      (node (ref "R4") (pin "2") (pinfunction "2_2") (pintype "bidirectional"))
      (node (ref "U$5") (pin "23") (pinfunction "P$23_23") (pintype "bidirectional"))
    )
    (net (code "69") (name "Net-(U$6-P$5)") (class "Default")
      (node (ref "U$6") (pin "5") (pinfunction "P$5_5") (pintype "output"))
      (node (ref "U$73") (pin "2") (pinfunction "C_2") (pintype "passive"))
    )
    (net (code "70") (name "Net-(U$6-P$6)") (class "Default")
      (node (ref "U$6") (pin "6") (pinfunction "P$6_6") (pintype "output"))
      (node (ref "U$74") (pin "2") (pinfunction "C_2") (pintype "passive"))
    )
    (net (code "71") (name "Net-(U$6-P$7)") (class "Default")
      (node (ref "U$6") (pin "7") (pinfunction "P$7_7") (pintype "output"))
      (node (ref "U$75") (pin "2") (pinfunction "C_2") (pintype "passive"))
    )
    (net (code "72") (name "Net-(U$6-P$8)") (class "Default")
      (node (ref "U$6") (pin "8") (pinfunction "P$8_8") (pintype "output"))
      (node (ref "U$76") (pin "2") (pinfunction "C_2") (pintype "passive"))
    )
    (net (code "73") (name "Net-(U$6-P$9)") (class "Default")
      (node (ref "U$6") (pin "9") (pinfunction "P$9_9") (pintype "output"))
      (node (ref "U$77") (pin "2") (pinfunction "C_2") (pintype "passive"))
    )
    (net (code "74") (name "Net-(U$6-P$10)") (class "Default")
      (node (ref "U$6") (pin "10") (pinfunction "P$10_10") (pintype "output"))
      (node (ref "U$78") (pin "2") (pinfunction "C_2") (pintype "passive"))
    )
    (net (code "75") (name "Net-(U$6-P$11)") (class "Default")
      (node (ref "U$6") (pin "11") (pinfunction "P$11_11") (pintype "output"))
      (node (ref "U$79") (pin "2") (pinfunction "C_2") (pintype "passive"))
    )
    (net (code "76") (name "Net-(U$6-P$12)") (class "Default")
      (node (ref "U$6") (pin "12") (pinfunction "P$12_12") (pintype "output"))
      (node (ref "U$80") (pin "2") (pinfunction "C_2") (pintype "passive"))
    )
    (net (code "77") (name "Net-(U$6-P$13)") (class "Default")
      (node (ref "U$6") (pin "13") (pinfunction "P$13_13") (pintype "output"))
      (node (ref "U$81") (pin "2") (pinfunction "C_2") (pintype "passive"))
    )
    (net (code "78") (name "Net-(U$6-P$14)") (class "Default")
      (node (ref "U$6") (pin "14") (pinfunction "P$14_14") (pintype "output"))
      (node (ref "U$82") (pin "2") (pinfunction "C_2") (pintype "passive"))
    )
    (net (code "79") (name "Net-(U$6-P$15)") (class "Default")
      (node (ref "U$6") (pin "15") (pinfunction "P$15_15") (pintype "output"))
      (node (ref "U$83") (pin "2") (pinfunction "C_2") (pintype "passive"))
    )
    (net (code "80") (name "Net-(U$6-P$16)") (class "Default")
      (node (ref "U$6") (pin "16") (pinfunction "P$16_16") (pintype "output"))
      (node (ref "U$84") (pin "2") (pinfunction "C_2") (pintype "passive"))
    )
    (net (code "81") (name "Net-(U$6-P$17)") (class "Default")
      (node (ref "U$6") (pin "17") (pinfunction "P$17_17") (pintype "output"))
      (node (ref "U$85") (pin "2") (pinfunction "C_2") (pintype "passive"))
    )
    (net (code "82") (name "Net-(U$6-P$18)") (class "Default")
      (node (ref "U$6") (pin "18") (pinfunction "P$18_18") (pintype "output"))
      (node (ref "U$86") (pin "2") (pinfunction "C_2") (pintype "passive"))
    )
    (net (code "83") (name "Net-(U$6-P$19)") (class "Default")
      (node (ref "U$6") (pin "19") (pinfunction "P$19_19") (pintype "output"))
      (node (ref "U$87") (pin "2") (pinfunction "C_2") (pintype "passive"))
    )
    (net (code "84") (name "Net-(U$6-P$20)") (class "Default")
      (node (ref "U$6") (pin "20") (pinfunction "P$20_20") (pintype "output"))
      (node (ref "U$88") (pin "2") (pinfunction "C_2") (pintype "passive"))
    )
    (net (code "85") (name "Net-(U$6-P$22)") (class "Default")
      (node (ref "U$6") (pin "22") (pinfunction "P$22_22") (pintype "output"))
      (node (ref "U$7") (pin "2") (pinfunction "P$2_2") (pintype "input"))
    )
    (net (code "86") (name "Net-(U$6-P$23)") (class "Default")
      (node (ref "R5") (pin "2") (pinfunction "2_2") (pintype "bidirectional"))
      (node (ref "U$6") (pin "23") (pinfunction "P$23_23") (pintype "bidirectional"))
    )
    (net (code "87") (name "Net-(U$7-P$5)") (class "Default")
      (node (ref "U$7") (pin "5") (pinfunction "P$5_5") (pintype "output"))
      (node (ref "U$89") (pin "2") (pinfunction "C_2") (pintype "passive"))
    )
    (net (code "88") (name "Net-(U$7-P$6)") (class "Default")
      (node (ref "U$7") (pin "6") (pinfunction "P$6_6") (pintype "output"))
      (node (ref "U$90") (pin "2") (pinfunction "C_2") (pintype "passive"))
    )
    (net (code "89") (name "Net-(U$7-P$7)") (class "Default")
      (node (ref "U$7") (pin "7") (pinfunction "P$7_7") (pintype "output"))
      (node (ref "U$91") (pin "2") (pinfunction "C_2") (pintype "passive"))
    )
    (net (code "90") (name "Net-(U$7-P$8)") (class "Default")
      (node (ref "U$7") (pin "8") (pinfunction "P$8_8") (pintype "output"))
      (node (ref "U$92") (pin "2") (pinfunction "C_2") (pintype "passive"))
    )
    (net (code "91") (name "Net-(U$7-P$9)") (class "Default")
      (node (ref "U$7") (pin "9") (pinfunction "P$9_9") (pintype "output"))
      (node (ref "U$93") (pin "2") (pinfunction "C_2") (pintype "passive"))
    )
    (net (code "92") (name "Net-(U$7-P$10)") (class "Default")
      (node (ref "U$7") (pin "10") (pinfunction "P$10_10") (pintype "output"))
      (node (ref "U$94") (pin "2") (pinfunction "C_2") (pintype "passive"))
    )
    (net (code "93") (name "Net-(U$7-P$11)") (class "Default")
      (node (ref "U$7") (pin "11") (pinfunction "P$11_11") (pintype "output"))
      (node (ref "U$95") (pin "2") (pinfunction "C_2") (pintype "passive"))
    )
    (net (code "94") (name "Net-(U$7-P$12)") (class "Default")
      (node (ref "U$7") (pin "12") (pinfunction "P$12_12") (pintype "output"))
      (node (ref "U$96") (pin "2") (pinfunction "C_2") (pintype "passive"))
    )
    (net (code "95") (name "Net-(U$7-P$13)") (class "Default")
      (node (ref "U$7") (pin "13") (pinfunction "P$13_13") (pintype "output"))
      (node (ref "U$97") (pin "2") (pinfunction "C_2") (pintype "passive"))
    )
    (net (code "96") (name "Net-(U$7-P$14)") (class "Default")
      (node (ref "U$7") (pin "14") (pinfunction "P$14_14") (pintype "output"))
      (node (ref "U$98") (pin "2") (pinfunction "C_2") (pintype "passive"))
    )
    (net (code "97") (name "Net-(U$7-P$15)") (class "Default")
      (node (ref "U$7") (pin "15") (pinfunction "P$15_15") (pintype "output"))
      (node (ref "U$99") (pin "2") (pinfunction "C_2") (pintype "passive"))
    )
    (net (code "98") (name "Net-(U$7-P$23)") (class "Default")
      (node (ref "R6") (pin "2") (pinfunction "2_2") (pintype "bidirectional"))
      (node (ref "U$7") (pin "23") (pinfunction "P$23_23") (pintype "bidirectional"))
    )
    (net (code "99") (name "Net-(U$8-P$23)") (class "Default")
      (node (ref "R7") (pin "2") (pinfunction "2_2") (pintype "bidirectional"))
      (node (ref "U$8") (pin "23") (pinfunction "P$23_23") (pintype "bidirectional"))
    )
    (net (code "100") (name "Net-(U$10-C)") (class "Default")
      (node (ref "U$10") (pin "2") (pinfunction "C_2") (pintype "passive"))
      (node (ref "U$2") (pin "6") (pinfunction "P$6_6") (pintype "output"))
    )
    (net (code "101") (name "Net-(U$11-C)") (class "Default")
      (node (ref "U$11") (pin "2") (pinfunction "C_2") (pintype "passive"))
      (node (ref "U$2") (pin "7") (pinfunction "P$7_7") (pintype "output"))
    )
    (net (code "102") (name "Net-(U$12-C)") (class "Default")
      (node (ref "U$12") (pin "2") (pinfunction "C_2") (pintype "passive"))
      (node (ref "U$2") (pin "8") (pinfunction "P$8_8") (pintype "output"))
    )
    (net (code "103") (name "Net-(U$13-C)") (class "Default")
      (node (ref "U$13") (pin "2") (pinfunction "C_2") (pintype "passive"))
      (node (ref "U$2") (pin "9") (pinfunction "P$9_9") (pintype "output"))
    )
    (net (code "104") (name "Net-(U$14-C)") (class "Default")
      (node (ref "U$14") (pin "2") (pinfunction "C_2") (pintype "passive"))
      (node (ref "U$2") (pin "10") (pinfunction "P$10_10") (pintype "output"))
    )
    (net (code "105") (name "Net-(U$15-C)") (class "Default")
      (node (ref "U$15") (pin "2") (pinfunction "C_2") (pintype "passive"))
      (node (ref "U$2") (pin "11") (pinfunction "P$11_11") (pintype "output"))
    )
    (net (code "106") (name "Net-(U$16-C)") (class "Default")
      (node (ref "U$16") (pin "2") (pinfunction "C_2") (pintype "passive"))
      (node (ref "U$2") (pin "12") (pinfunction "P$12_12") (pintype "output"))
    )
    (net (code "107") (name "Net-(U$17-C)") (class "Default")
      (node (ref "U$17") (pin "2") (pinfunction "C_2") (pintype "passive"))
      (node (ref "U$2") (pin "13") (pinfunction "P$13_13") (pintype "output"))
    )
    (net (code "108") (name "Net-(U$18-C)") (class "Default")
      (node (ref "U$18") (pin "2") (pinfunction "C_2") (pintype "passive"))
      (node (ref "U$2") (pin "14") (pinfunction "P$14_14") (pintype "output"))
    )
    (net (code "109") (name "Net-(U$19-C)") (class "Default")
      (node (ref "U$19") (pin "2") (pinfunction "C_2") (pintype "passive"))
      (node (ref "U$2") (pin "15") (pinfunction "P$15_15") (pintype "output"))
    )
    (net (code "110") (name "Net-(U$25-C)") (class "Default")
      (node (ref "U$25") (pin "2") (pinfunction "C_2") (pintype "passive"))
      (node (ref "U$3") (pin "5") (pinfunction "P$5_5") (pintype "output"))
    )
    (net (code "111") (name "Net-(U$26-C)") (class "Default")
      (node (ref "U$26") (pin "2") (pinfunction "C_2") (pintype "passive"))
      (node (ref "U$3") (pin "6") (pinfunction "P$6_6") (pintype "output"))
    )
    (net (code "112") (name "Net-(U$27-C)") (class "Default")
      (node (ref "U$27") (pin "2") (pinfunction "C_2") (pintype "passive"))
      (node (ref "U$3") (pin "7") (pinfunction "P$7_7") (pintype "output"))
    )
    (net (code "113") (name "Net-(U$28-C)") (class "Default")
      (node (ref "U$28") (pin "2") (pinfunction "C_2") (pintype "passive"))
      (node (ref "U$3") (pin "8") (pinfunction "P$8_8") (pintype "output"))
    )
    (net (code "114") (name "Net-(U$29-C)") (class "Default")
      (node (ref "U$29") (pin "2") (pinfunction "C_2") (pintype "passive"))
      (node (ref "U$3") (pin "9") (pinfunction "P$9_9") (pintype "output"))
    )
    (net (code "115") (name "Net-(U$100-C)") (class "Default")
      (node (ref "U$100") (pin "2") (pinfunction "C_2") (pintype "passive"))
      (node (ref "U$7") (pin "16") (pinfunction "P$16_16") (pintype "output"))
    )
    (net (code "116") (name "Net-(U$101-C)") (class "Default")
      (node (ref "U$101") (pin "2") (pinfunction "C_2") (pintype "passive"))
      (node (ref "U$7") (pin "17") (pinfunction "P$17_17") (pintype "output"))
    )
    (net (code "117") (name "Net-(U$102-C)") (class "Default")
      (node (ref "U$102") (pin "2") (pinfunction "C_2") (pintype "passive"))
      (node (ref "U$7") (pin "18") (pinfunction "P$18_18") (pintype "output"))
    )
    (net (code "118") (name "Net-(U$103-C)") (class "Default")
      (node (ref "U$103") (pin "2") (pinfunction "C_2") (pintype "passive"))
      (node (ref "U$7") (pin "19") (pinfunction "P$19_19") (pintype "output"))
    )
    (net (code "119") (name "Net-(U$104-C)") (class "Default")
      (node (ref "U$104") (pin "2") (pinfunction "C_2") (pintype "passive"))
      (node (ref "U$7") (pin "20") (pinfunction "P$20_20") (pintype "output"))
    )
    (net (code "120") (name "Net-(U$105-C)") (class "Default")
      (node (ref "U$105") (pin "2") (pinfunction "C_2") (pintype "passive"))
      (node (ref "U$8") (pin "5") (pinfunction "P$5_5") (pintype "output"))
    )
    (net (code "121") (name "Net-(U$106-C)") (class "Default")
      (node (ref "U$106") (pin "2") (pinfunction "C_2") (pintype "passive"))
      (node (ref "U$8") (pin "6") (pinfunction "P$6_6") (pintype "output"))
    )
    (net (code "122") (name "Net-(U$107-C)") (class "Default")
      (node (ref "U$107") (pin "2") (pinfunction "C_2") (pintype "passive"))
      (node (ref "U$8") (pin "7") (pinfunction "P$7_7") (pintype "output"))
    )
    (net (code "123") (name "Net-(U$108-C)") (class "Default")
      (node (ref "U$108") (pin "2") (pinfunction "C_2") (pintype "passive"))
      (node (ref "U$8") (pin "8") (pinfunction "P$8_8") (pintype "output"))
    )
    (net (code "124") (name "Net-(U$109-C)") (class "Default")
      (node (ref "U$109") (pin "2") (pinfunction "C_2") (pintype "passive"))
      (node (ref "U$8") (pin "9") (pinfunction "P$9_9") (pintype "output"))
    )
    (net (code "125") (name "Net-(U$110-C)") (class "Default")
      (node (ref "U$110") (pin "2") (pinfunction "C_2") (pintype "passive"))
      (node (ref "U$8") (pin "10") (pinfunction "P$10_10") (pintype "output"))
    )
    (net (code "126") (name "Net-(U$111-C)") (class "Default")
      (node (ref "U$111") (pin "2") (pinfunction "C_2") (pintype "passive"))
      (node (ref "U$8") (pin "11") (pinfunction "P$11_11") (pintype "output"))
    )
    (net (code "127") (name "Net-(U$112-C)") (class "Default")
      (node (ref "U$112") (pin "2") (pinfunction "C_2") (pintype "passive"))
      (node (ref "U$8") (pin "12") (pinfunction "P$12_12") (pintype "output"))
    )
    (net (code "128") (name "Net-(U$113-C)") (class "Default")
      (node (ref "U$113") (pin "2") (pinfunction "C_2") (pintype "passive"))
      (node (ref "U$8") (pin "13") (pinfunction "P$13_13") (pintype "output"))
    )
    (net (code "129") (name "Net-(U$114-C)") (class "Default")
      (node (ref "U$114") (pin "2") (pinfunction "C_2") (pintype "passive"))
      (node (ref "U$8") (pin "14") (pinfunction "P$14_14") (pintype "output"))
    )
    (net (code "130") (name "Net-(U$115-C)") (class "Default")
      (node (ref "U$115") (pin "2") (pinfunction "C_2") (pintype "passive"))
      (node (ref "U$8") (pin "15") (pinfunction "P$15_15") (pintype "output"))
    )
    (net (code "131") (name "Net-(U$116-C)") (class "Default")
      (node (ref "U$116") (pin "2") (pinfunction "C_2") (pintype "passive"))
      (node (ref "U$8") (pin "16") (pinfunction "P$16_16") (pintype "output"))
    )
    (net (code "132") (name "Net-(U$117-C)") (class "Default")
      (node (ref "U$117") (pin "2") (pinfunction "C_2") (pintype "passive"))
      (node (ref "U$8") (pin "17") (pinfunction "P$17_17") (pintype "output"))
    )
    (net (code "133") (name "Net-(U$118-C)") (class "Default")
      (node (ref "U$118") (pin "2") (pinfunction "C_2") (pintype "passive"))
      (node (ref "U$8") (pin "18") (pinfunction "P$18_18") (pintype "output"))
    )
    (net (code "134") (name "Net-(U$119-C)") (class "Default")
      (node (ref "U$119") (pin "2") (pinfunction "C_2") (pintype "passive"))
      (node (ref "U$8") (pin "19") (pinfunction "P$19_19") (pintype "output"))
    )
    (net (code "135") (name "Net-(U$120-C)") (class "Default")
      (node (ref "U$120") (pin "2") (pinfunction "C_2") (pintype "passive"))
      (node (ref "U$8") (pin "20") (pinfunction "P$20_20") (pintype "output"))
    )
    (net (code "136") (name "Net-(U$121-2)") (class "Default")
      (node (ref "R1") (pin "1") (pinfunction "1_1") (pintype "bidirectional"))
      (node (ref "U$121") (pin "P$2") (pinfunction "2_P$2") (pintype "passive"))
    )
    (net (code "137") (name "Net-(U$122-2)") (class "Default")
      (node (ref "R2") (pin "1") (pinfunction "1_1") (pintype "bidirectional"))
      (node (ref "U$122") (pin "P$2") (pinfunction "2_P$2") (pintype "passive"))
    )
    (net (code "138") (name "Net-(U$123-2)") (class "Default")
      (node (ref "R3") (pin "1") (pinfunction "1_1") (pintype "bidirectional"))
      (node (ref "U$123") (pin "P$2") (pinfunction "2_P$2") (pintype "passive"))
    )
    (net (code "139") (name "Net-(U$124-2)") (class "Default")
      (node (ref "R4") (pin "1") (pinfunction "1_1") (pintype "bidirectional"))
      (node (ref "U$124") (pin "P$2") (pinfunction "2_P$2") (pintype "passive"))
    )
    (net (code "140") (name "Net-(U$125-2)") (class "Default")
      (node (ref "R5") (pin "1") (pinfunction "1_1") (pintype "bidirectional"))
      (node (ref "U$125") (pin "P$2") (pinfunction "2_P$2") (pintype "passive"))
    )
    (net (code "141") (name "Net-(U$126-2)") (class "Default")
      (node (ref "R6") (pin "1") (pinfunction "1_1") (pintype "bidirectional"))
      (node (ref "U$126") (pin "P$2") (pinfunction "2_P$2") (pintype "passive"))
    )
    (net (code "142") (name "Net-(U$127-2)") (class "Default")
      (node (ref "R7") (pin "1") (pinfunction "1_1") (pintype "bidirectional"))
      (node (ref "U$127") (pin "P$2") (pinfunction "2_P$2") (pintype "passive"))
    )
    (net (code "143") (name "unconnected-(U$1-0{slash}RX1{slash}MOSI1{slash}T-Pad0)") (class "Default")
      (node (ref "U$1") (pin "0") (pinfunction "0/RX1/MOSI1/T_0") (pintype "bidirectional"))
    )
    (net (code "144") (name "unconnected-(U$1-1{slash}TX1{slash}MISO1{slash}T-Pad1)") (class "Default")
      (node (ref "U$1") (pin "1") (pinfunction "1/TX1/MISO1/T_1") (pintype "bidirectional"))
    )
    (net (code "145") (name "unconnected-(U$1-2{slash}PWM-Pad2)") (class "Default")
      (node (ref "U$1") (pin "2") (pinfunction "2/PWM_2") (pintype "bidirectional"))
    )
    (net (code "146") (name "unconnected-(U$1-3{slash}CAN0-TX{slash}SCL2{slash}PWM-Pad3)") (class "Default")
      (node (ref "U$1") (pin "3") (pinfunction "3/CAN0-TX/SCL2/PWM_3") (pintype "bidirectional"))
    )
    (net (code "147") (name "unconnected-(U$1-12{slash}MISO0-Pad12)") (class "Default")
      (node (ref "U$1") (pin "12") (pinfunction "12/MISO0_12") (pintype "bidirectional"))
    )
    (net (code "148") (name "unconnected-(U$1-13{slash}SCK0{slash}LED-Pad13)") (class "Default")
      (node (ref "U$1") (pin "13") (pinfunction "13/SCK0/LED_13") (pintype "bidirectional"))
    )
    (net (code "149") (name "unconnected-(U$1-14{slash}A0{slash}PWM-Pad14{slash}A0)") (class "Default")
      (node (ref "U$1") (pin "14/A0") (pinfunction "14/A0/PWM_14/A0") (pintype "bidirectional"))
    )
    (net (code "150") (name "unconnected-(U$1-15{slash}A1{slash}T-Pad15{slash}A1)") (class "Default")
      (node (ref "U$1") (pin "15/A1") (pinfunction "15/A1/T_15/A1") (pintype "bidirectional"))
    )
    (net (code "151") (name "unconnected-(U$1-16{slash}A2{slash}T{slash}PWM-Pad16{slash}A2)") (class "Default")
      (node (ref "U$1") (pin "16/A2") (pinfunction "16/A2/T/PWM_16/A2") (pintype "bidirectional"))
    )
    (net (code "152") (name "unconnected-(U$1-17{slash}A3{slash}T{slash}PWM-Pad17{slash}A3)") (class "Default")
      (node (ref "U$1") (pin "17/A3") (pinfunction "17/A3/T/PWM_17/A3") (pintype "bidirectional"))
    )
    (net (code "153") (name "unconnected-(U$1-18{slash}A4{slash}T{slash}SDA0-Pad18{slash}A4)") (class "Default")
      (node (ref "U$1") (pin "18/A4") (pinfunction "18/A4/T/SDA0_18/A4") (pintype "bidirectional"))
    )
    (net (code "154") (name "unconnected-(U$1-19{slash}A5{slash}T{slash}SCL0-Pad19{slash}A5)") (class "Default")
      (node (ref "U$1") (pin "19/A5") (pinfunction "19/A5/T/SCL0_19/A5") (pintype "bidirectional"))
    )
    (net (code "155") (name "unconnected-(U$1-20{slash}A6{slash}PWM-Pad20{slash}A6)") (class "Default")
      (node (ref "U$1") (pin "20/A6") (pinfunction "20/A6/PWM_20/A6") (pintype "bidirectional"))
    )
    (net (code "156") (name "unconnected-(U$1-21{slash}A7{slash}PWM-Pad21{slash}A7)") (class "Default")
      (node (ref "U$1") (pin "21/A7") (pinfunction "21/A7/PWM_21/A7") (pintype "bidirectional"))
    )
    (net (code "157") (name "unconnected-(U$1-22{slash}A8{slash}T{slash}PWM-Pad22{slash}A8)") (class "Default")
      (node (ref "U$1") (pin "22/A8") (pinfunction "22/A8/T/PWM_22/A8") (pintype "bidirectional"))
    )
    (net (code "158") (name "unconnected-(U$1-23{slash}A9{slash}T{slash}PWM-Pad23{slash}A9)") (class "Default")
      (node (ref "U$1") (pin "23/A9") (pinfunction "23/A9/T/PWM_23/A9") (pintype "bidirectional"))
    )
    (net (code "159") (name "unconnected-(U$1-29{slash}T{slash}PWM-Pad29)") (class "Default")
      (node (ref "U$1") (pin "29") (pinfunction "29/T/PWM_29") (pintype "bidirectional"))
    )
    (net (code "160") (name "unconnected-(U$1-30{slash}T{slash}PWM-Pad30)") (class "Default")
      (node (ref "U$1") (pin "30") (pinfunction "30/T/PWM_30") (pintype "bidirectional"))
    )
    (net (code "161") (name "unconnected-(U$1-31{slash}A12{slash}RX4-Pad31{slash}A12)") (class "Default")
      (node (ref "U$1") (pin "31/A12") (pinfunction "31/A12/RX4_31/A12") (pintype "bidirectional"))
    )
    (net (code "162") (name "unconnected-(U$1-32{slash}A13{slash}TX4-Pad32{slash}A13)") (class "Default")
      (node (ref "U$1") (pin "32/A13") (pinfunction "32/A13/TX4_32/A13") (pintype "bidirectional"))
    )
    (net (code "163") (name "unconnected-(U$1-33{slash}A14{slash}TX5{slash}CAN1-TX-Pad33{slash}A14)") (class "Default")
      (node (ref "U$1") (pin "33/A14") (pinfunction "33/A14/TX5/CAN1-TX_33/A14") (pintype "bidirectional"))
    )
    (net (code "164") (name "unconnected-(U$1-34{slash}A15{slash}RX5{slash}CAN1-RX-Pad34{slash}A15)") (class "Default")
      (node (ref "U$1") (pin "34/A15") (pinfunction "34/A15/RX5/CAN1-RX_34/A15") (pintype "bidirectional"))
    )
    (net (code "165") (name "unconnected-(U$1-35{slash}A16{slash}PWM-Pad35{slash}A16)") (class "Default")
      (node (ref "U$1") (pin "35/A16") (pinfunction "35/A16/PWM_35/A16") (pintype "bidirectional"))
    )
    (net (code "166") (name "unconnected-(U$1-36{slash}A17{slash}PWM-Pad36{slash}A17)") (class "Default")
      (node (ref "U$1") (pin "36/A17") (pinfunction "36/A17/PWM_36/A17") (pintype "bidirectional"))
    )
    (net (code "167") (name "unconnected-(U$1-37{slash}A18{slash}SCL1{slash}PWM-Pad37{slash}A18)") (class "Default")
      (node (ref "U$1") (pin "37/A18") (pinfunction "37/A18/SCL1/PWM_37/A18") (pintype "bidirectional"))
    )
    (net (code "168") (name "unconnected-(U$1-38{slash}A19{slash}SDA1{slash}PWM-Pad38{slash}A19)") (class "Default")
      (node (ref "U$1") (pin "38/A19") (pinfunction "38/A19/SDA1/PWM_38/A19") (pintype "bidirectional"))
    )
    (net (code "169") (name "unconnected-(U$1-A21{slash}DAC0-PadA21)") (class "Default")
      (node (ref "U$1") (pin "A21") (pinfunction "A21/DAC0_A21") (pintype "bidirectional"))
    )
    (net (code "170") (name "unconnected-(U$1-A22{slash}DAC1-PadA22)") (class "Default")
      (node (ref "U$1") (pin "A22") (pinfunction "A22/DAC1_A22") (pintype "bidirectional"))
    )
    (net (code "171") (name "unconnected-(U$1-Pad24)") (class "Default")
      (node (ref "U$1") (pin "24") (pinfunction "24_24") (pintype "bidirectional"))
    )
    (net (code "172") (name "unconnected-(U$1-Pad25)") (class "Default")
      (node (ref "U$1") (pin "25") (pinfunction "25_25") (pintype "bidirectional"))
    )
    (net (code "173") (name "unconnected-(U$1-Pad26)") (class "Default")
      (node (ref "U$1") (pin "26") (pinfunction "26_26") (pintype "bidirectional"))
    )
    (net (code "174") (name "unconnected-(U$1-Pad27)") (class "Default")
      (node (ref "U$1") (pin "27") (pinfunction "27_27") (pintype "bidirectional"))
    )
    (net (code "175") (name "unconnected-(U$1-Pad28)") (class "Default")
      (node (ref "U$1") (pin "28") (pinfunction "28_28") (pintype "bidirectional"))
    )
    (net (code "176") (name "unconnected-(U$1-Pad39{slash}A20)") (class "Default")
      (node (ref "U$1") (pin "39/A20") (pinfunction "39/A20_39/A20") (pintype "bidirectional"))
    )
    (net (code "177") (name "unconnected-(U$7-P$22-Pad22)") (class "Default")
      (node (ref "U$7") (pin "22") (pinfunction "P$22_22") (pintype "output"))
    )
    (net (code "178") (name "unconnected-(U$8-P$22-Pad22)") (class "Default")
      (node (ref "U$8") (pin "22") (pinfunction "P$22_22") (pintype "output"))
    )
    (net (code "179") (name "unconnected-(U$121-1-PadP$1)") (class "Default")
      (node (ref "U$121") (pin "P$1") (pinfunction "1_P$1") (pintype "passive"))
    )
    (net (code "180") (name "unconnected-(U$122-1-PadP$1)") (class "Default")
      (node (ref "U$122") (pin "P$1") (pinfunction "1_P$1") (pintype "passive"))
    )
    (net (code "181") (name "unconnected-(U$123-1-PadP$1)") (class "Default")
      (node (ref "U$123") (pin "P$1") (pinfunction "1_P$1") (pintype "passive"))
    )
    (net (code "182") (name "unconnected-(U$124-1-PadP$1)") (class "Default")
      (node (ref "U$124") (pin "P$1") (pinfunction "1_P$1") (pintype "passive"))
    )
    (net (code "183") (name "unconnected-(U$125-1-PadP$1)") (class "Default")
      (node (ref "U$125") (pin "P$1") (pinfunction "1_P$1") (pintype "passive"))
    )
    (net (code "184") (name "unconnected-(U$126-1-PadP$1)") (class "Default")
      (node (ref "U$126") (pin "P$1") (pinfunction "1_P$1") (pintype "passive"))
    )
    (net (code "185") (name "unconnected-(U$127-1-PadP$1)") (class "Default")
      (node (ref "U$127") (pin "P$1") (pinfunction "1_P$1") (pintype "passive"))
    )
  )
)
